# Simple-Charger-LiIon-OpampBased-LM324.net
KiCad netlist of a schematic drawn in EAGLE
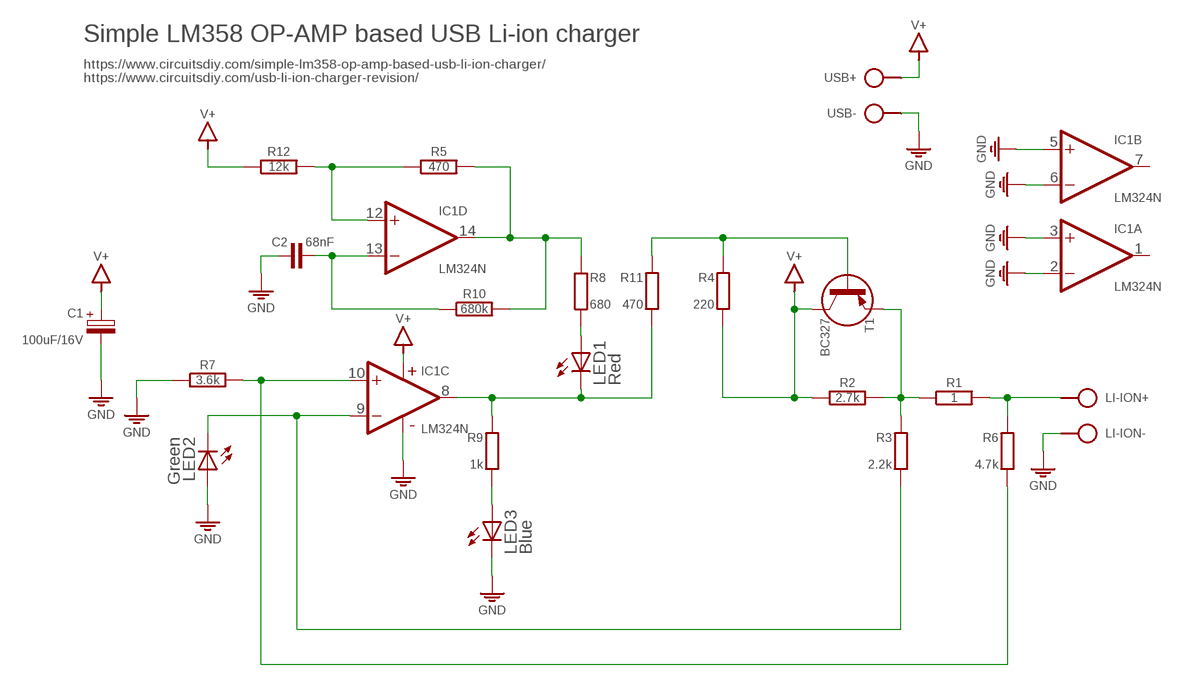
[diagram p0: schematic, sheet 1]

(export (version "E")
  (design (tool "Eeschema 10.0.6"))
  (components
    (comp (ref "C1")
      (value "100uF/16V")
      (footprint "eagle-import:E2,5-5_V")
      (libsource (lib "eagle-import") (part "CPOLE2,5-5/V"))
    )
    (comp (ref "C2")
      (value "68nF")
      (footprint "eagle-import:C050-020X044_V")
      (libsource (lib "eagle-import") (part "C-H050-020X044/V"))
    )
    (comp (ref "IC1")
      (value "LM324N")
      (footprint "eagle-import:DIL14")
      (libsource (lib "eagle-import") (part "LM324N"))
    )
    (comp (ref "LED1")
      (value "Red")
      (footprint "eagle-import:LED3MM")
      (libsource (lib "eagle-import") (part "LED3MM"))
    )
    (comp (ref "LED2")
      (value "Green")
      (footprint "eagle-import:LED3MM")
      (libsource (lib "eagle-import") (part "LED3MM"))
    )
    (comp (ref "LED3")
      (value "Blue")
      (footprint "eagle-import:LED3MM")
      (libsource (lib "eagle-import") (part "LED3MM"))
    )
    (comp (ref "LI-ION")
      (value "SPAD+-+-")
      (footprint "eagle-import:SPAD+-")
      (libsource (lib "eagle-import") (part "SPAD+-+-"))
    )
    (comp (ref "R1")
      (value "1")
      (footprint "eagle-import:0204_10-V")
      (libsource (lib "eagle-import") (part "R-H0204/10-V"))
    )
    (comp (ref "R2")
      (value "2.7k")
      (footprint "eagle-import:0204_10-V")
      (libsource (lib "eagle-import") (part "R-H0204/10-V"))
    )
    (comp (ref "R3")
      (value "2.2k")
      (footprint "eagle-import:0204_10-V")
      (libsource (lib "eagle-import") (part "R0204/10-V"))
    )
    (comp (ref "R4")
      (value "220")
      (footprint "eagle-import:0204_10")
      (libsource (lib "eagle-import") (part "R0204/10"))
    )
    (comp (ref "R5")
      (value "470")
      (footprint "eagle-import:0204_10")
      (libsource (lib "eagle-import") (part "R-H0204/10"))
    )
    (comp (ref "R6")
      (value "4.7k")
      (footprint "eagle-import:0204_10-V")
      (libsource (lib "eagle-import") (part "R0204/10-V"))
    )
    (comp (ref "R7")
      (value "3.6k")
      (footprint "eagle-import:0204_10-V")
      (libsource (lib "eagle-import") (part "R-H0204/10-V"))
    )
    (comp (ref "R8")
      (value "680")
      (footprint "eagle-import:0204_10")
      (libsource (lib "eagle-import") (part "R0204/10"))
    )
    (comp (ref "R9")
      (value "1k")
      (footprint "eagle-import:0204_10-V")
      (libsource (lib "eagle-import") (part "R0204/10-V"))
    )
    (comp (ref "R10")
      (value "680k")
      (footprint "eagle-import:0204_2V")
      (libsource (lib "eagle-import") (part "R-H0204/2V"))
    )
    (comp (ref "R11")
      (value "470")
      (footprint "eagle-import:0204_10-V")
      (libsource (lib "eagle-import") (part "R0204/10-V"))
    )
    (comp (ref "R12")
      (value "12k")
      (footprint "eagle-import:0204_10-V")
      (libsource (lib "eagle-import") (part "R-H0204/10-V"))
    )
    (comp (ref "T1")
      (value "BC327")
      (footprint "eagle-import:TO92")
      (libsource (lib "eagle-import") (part "BC327"))
    )
    (comp (ref "USB")
      (value "SPAD+--+")
      (footprint "eagle-import:SPAD-+")
      (libsource (lib "eagle-import") (part "SPAD+--+"))
    )
  )
  (nets
    (net (code "1") (name "GND") (class "Default")
      (node (ref "C1") (pin "-") (pinfunction "-_-") (pintype "passive"))
      (node (ref "C2") (pin "1") (pinfunction "1_1") (pintype "passive"))
      (node (ref "IC1") (pin "11") (pinfunction "V-_11") (pintype "power_in"))
      (node (ref "IC1") (pin "2") (pinfunction "-IN_2") (pintype "input"))
      (node (ref "IC1") (pin "3") (pinfunction "+IN_3") (pintype "input"))
      (node (ref "IC1") (pin "5") (pinfunction "+IN_5") (pintype "input"))
      (node (ref "IC1") (pin "6") (pinfunction "-IN_6") (pintype "input"))
      (node (ref "LED2") (pin "A") (pinfunction "A_A") (pintype "passive"))
      (node (ref "LED3") (pin "K") (pinfunction "C_K") (pintype "passive"))
      (node (ref "LI-ION") (pin "1") (pinfunction "P$1_1") (pintype "passive"))
      (node (ref "R7") (pin "1") (pinfunction "1_1") (pintype "passive"))
      (node (ref "USB") (pin "1") (pinfunction "P$1_1") (pintype "passive"))
    )
    (net (code "2") (name "Net-(IC1C-+IN)") (class "Default")
      (node (ref "IC1") (pin "10") (pinfunction "+IN_10") (pintype "input"))
      (node (ref "R6") (pin "2") (pinfunction "2_2") (pintype "passive"))
      (node (ref "R7") (pin "2") (pinfunction "2_2") (pintype "passive"))
    )
    (net (code "3") (name "Net-(IC1C--IN)") (class "Default")
      (node (ref "IC1") (pin "9") (pinfunction "-IN_9") (pintype "input"))
      (node (ref "LED2") (pin "K") (pinfunction "C_K") (pintype "passive"))
      (node (ref "R3") (pin "2") (pinfunction "2_2") (pintype "passive"))
    )
    (net (code "4") (name "Net-(IC1C-OUT)") (class "Default")
      (node (ref "IC1") (pin "8") (pinfunction "OUT_8") (pintype "output"))
      (node (ref "LED1") (pin "K") (pinfunction "C_K") (pintype "passive"))
      (node (ref "R11") (pin "2") (pinfunction "2_2") (pintype "passive"))
      (node (ref "R9") (pin "1") (pinfunction "1_1") (pintype "passive"))
    )
    (net (code "5") (name "Net-(IC1D-+IN)") (class "Default")
      (node (ref "IC1") (pin "12") (pinfunction "+IN_12") (pintype "input"))
      (node (ref "R12") (pin "2") (pinfunction "2_2") (pintype "passive"))
      (node (ref "R5") (pin "1") (pinfunction "1_1") (pintype "passive"))
    )
    (net (code "6") (name "Net-(IC1D--IN)") (class "Default")
      (node (ref "C2") (pin "2") (pinfunction "2_2") (pintype "passive"))
      (node (ref "IC1") (pin "13") (pinfunction "-IN_13") (pintype "input"))
      (node (ref "R10") (pin "1") (pinfunction "1_1") (pintype "passive"))
    )
    (net (code "7") (name "Net-(IC1D-OUT)") (class "Default")
      (node (ref "IC1") (pin "14") (pinfunction "OUT_14") (pintype "output"))
      (node (ref "R10") (pin "2") (pinfunction "2_2") (pintype "passive"))
      (node (ref "R5") (pin "2") (pinfunction "2_2") (pintype "passive"))
      (node (ref "R8") (pin "1") (pinfunction "1_1") (pintype "passive"))
    )
    (net (code "8") (name "Net-(LED1-PadA)") (class "Default")
      (node (ref "LED1") (pin "A") (pinfunction "A_A") (pintype "passive"))
      (node (ref "R8") (pin "2") (pinfunction "2_2") (pintype "passive"))
    )
    (net (code "9") (name "Net-(LED3-PadA)") (class "Default")
      (node (ref "LED3") (pin "A") (pinfunction "A_A") (pintype "passive"))
      (node (ref "R9") (pin "2") (pinfunction "2_2") (pintype "passive"))
    )
    (net (code "10") (name "Net-(LI-IONA-P$1)") (class "Default")
      (node (ref "LI-ION") (pin "2") (pinfunction "P$1_2") (pintype "passive"))
      (node (ref "R1") (pin "2") (pinfunction "2_2") (pintype "passive"))
      (node (ref "R6") (pin "1") (pinfunction "1_1") (pintype "passive"))
    )
    (net (code "11") (name "Net-(T1-B)") (class "Default")
      (node (ref "R11") (pin "1") (pinfunction "1_1") (pintype "passive"))
      (node (ref "R4") (pin "1") (pinfunction "1_1") (pintype "passive"))
      (node (ref "T1") (pin "2") (pinfunction "B_2") (pintype "passive"))
    )
    (net (code "12") (name "Net-(T1-E)") (class "Default")
      (node (ref "R1") (pin "1") (pinfunction "1_1") (pintype "passive"))
      (node (ref "R2") (pin "2") (pinfunction "2_2") (pintype "passive"))
      (node (ref "R3") (pin "1") (pinfunction "1_1") (pintype "passive"))
      (node (ref "T1") (pin "3") (pinfunction "E_3") (pintype "passive"))
    )
    (net (code "13") (name "V+") (class "Default")
      (node (ref "C1") (pin "+") (pinfunction "+_+") (pintype "passive"))
      (node (ref "IC1") (pin "4") (pinfunction "V+_4") (pintype "power_in"))
      (node (ref "R12") (pin "1") (pinfunction "1_1") (pintype "passive"))
      (node (ref "R2") (pin "1") (pinfunction "1_1") (pintype "passive"))
      (node (ref "R4") (pin "2") (pinfunction "2_2") (pintype "passive"))
      (node (ref "T1") (pin "1") (pinfunction "C_1") (pintype "passive"))
      (node (ref "USB") (pin "2") (pinfunction "P$1_2") (pintype "passive"))
    )
    (net (code "14") (name "unconnected-(IC1A-OUT-Pad1)") (class "Default")
      (node (ref "IC1") (pin "1") (pinfunction "OUT_1") (pintype "output"))
    )
    (net (code "15") (name "unconnected-(IC1B-OUT-Pad7)") (class "Default")
      (node (ref "IC1") (pin "7") (pinfunction "OUT_7") (pintype "output"))
    )
  )
)
